# voltage-detection.net
KiCad netlist of a schematic drawn in Altium Designer
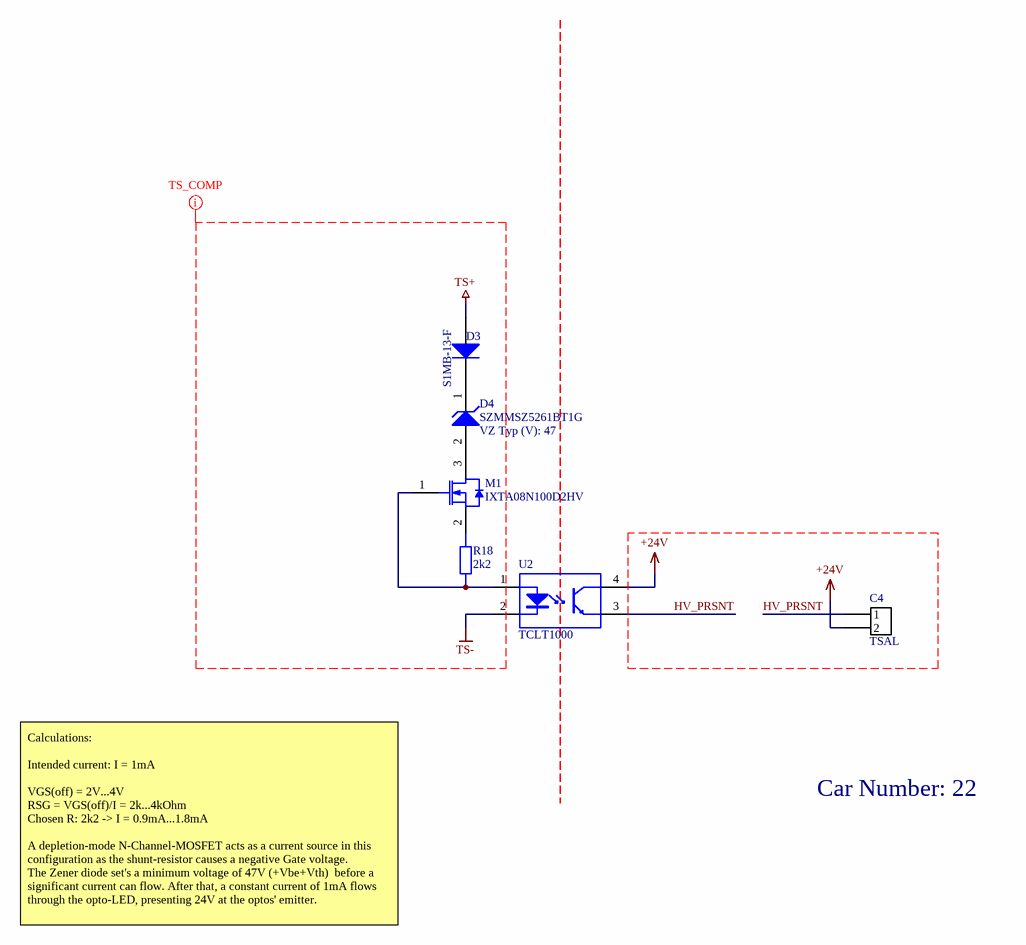
[diagram p0: voltage-detection.SchDoc]

(export (version "E")
  (design (tool "Eeschema 10.0.6"))
  (components
    (comp (ref "C4")
      (value "TSAL")
      (footprint "43650-0200")
      (description "Molex Micro-Fit 3.0 2-Pin\r\n600V\r\n8.5A")
      (libsource (lib "Standardbauteile") (part "MicroFit3.0 2-Pin"))
    )
    (comp (ref "D3")
      (value "S1MB-13-F")
      (footprint "DIOD-SMB-2_V")
      (fields (field (name "MANUFACTURER") "Diodes Inc"))
      (libsource (lib "Altium Content Vault") (part "D-AK-2"))
    )
    (comp (ref "D4")
      (value "SZMMSZ5261BT1G")
      (footprint "ONSC-SOD-123-2-425-04_V")
      (description "Zener Voltage Regulator, 500 mW, 2-Pin SOD-123, Pb-Free, Tape and Reel")
      (fields (field (name "VZ TYP (V)") "47") (field (name "MANUFACTURER") "On Semiconductor"))
      (libsource (lib "Altium Content Vault") (part "ONSC-K1A2-2"))
    )
    (comp (ref "M1")
      (value "IXTA08N100D2HV")
      (footprint "IXYS_TO-263HV")
      (description "D2 Series - 100V - 1700V N-Channel Depletion Mode Power MOSFETs, TO-263HV, RoHS")
      (fields (field (name "MANUFACTURER") "Littelfuse"))
      (libsource (lib "Leon") (part "IXTA08N100D2HV"))
    )
    (comp (ref "R18")
      (value "2k2")
      (footprint "STACKPOLE CSR0603")
      (description "Resistor with multiple footprints")
      (fields (field (name "Comment") "SMD Resistor"))
      (libsource (lib "Standardbauteile") (part "SMD Resistor"))
    )
    (comp (ref "U2")
      (value "TCLT1000")
      (footprint "VISH-SOP4L-4_V")
      (fields (field (name "MANUFACTURER") "Vishay/Semiconductor"))
      (libsource (lib "Altium Content Vault") (part "OPTO-ACEC-4"))
    )
  )
  (nets
    (net (code "1") (name "+24V") (class "Default")
      (node (ref "C4") (pin "2") (pinfunction "2_2") (pintype "passive"))
      (node (ref "U2") (pin "4") (pinfunction "C_4") (pintype "passive"))
    )
    (net (code "2") (name "/HV_PRSNT") (class "Default")
      (node (ref "C4") (pin "1") (pinfunction "1_1") (pintype "passive"))
      (node (ref "U2") (pin "3") (pinfunction "E_3") (pintype "passive"))
    )
    (net (code "3") (name "Net-(D3-K)") (class "Default")
      (node (ref "D3") (pin "2") (pinfunction "K_2") (pintype "passive"))
      (node (ref "D4") (pin "1") (pinfunction "K_1") (pintype "passive"))
    )
    (net (code "4") (name "Net-(D4-A)") (class "Default")
      (node (ref "D4") (pin "2") (pinfunction "A_2") (pintype "passive"))
      (node (ref "M1") (pin "3") (pinfunction "DRAIN_3") (pintype "passive"))
    )
    (net (code "5") (name "Net-(M1-GATE)") (class "Default")
      (node (ref "M1") (pin "1") (pinfunction "GATE_1") (pintype "passive"))
      (node (ref "R18") (pin "1") (pinfunction "1_1") (pintype "passive"))
      (node (ref "U2") (pin "1") (pinfunction "A_1") (pintype "passive"))
    )
    (net (code "6") (name "Net-(M1-SOURCE)") (class "Default")
      (node (ref "M1") (pin "2") (pinfunction "SOURCE_2") (pintype "passive"))
      (node (ref "R18") (pin "2") (pinfunction "2_2") (pintype "passive"))
    )
    (net (code "7") (name "TS+") (class "Default")
      (node (ref "D3") (pin "1") (pinfunction "A_1") (pintype "passive"))
    )
    (net (code "8") (name "TS-") (class "Default")
      (node (ref "U2") (pin "2") (pinfunction "C_2") (pintype "passive"))
    )
  )
)
